# covox.net
KiCad netlist of a schematic drawn in EAGLE
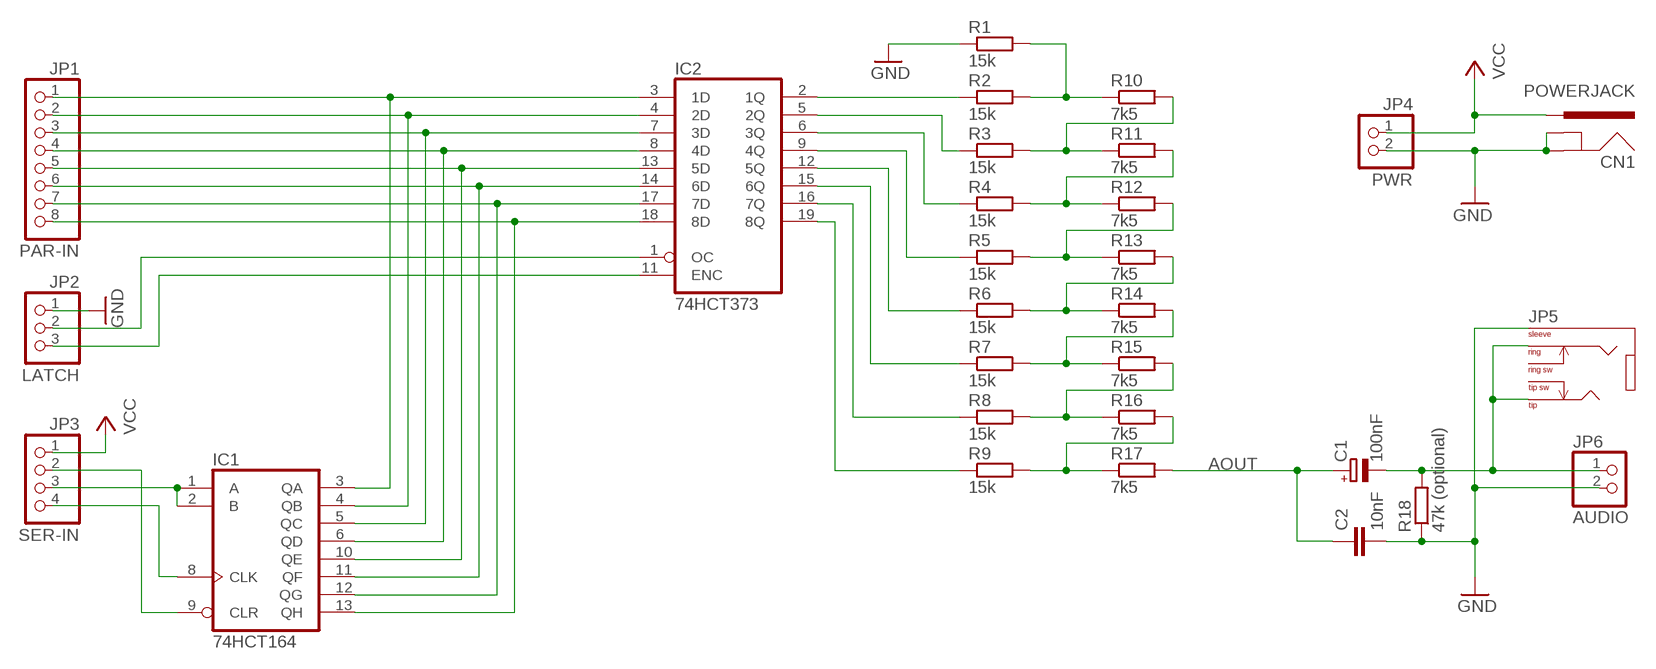
[diagram p0: schematic, sheet 1]

(export (version "E")
  (design (tool "Eeschema 10.0.6"))
  (components
    (comp (ref "C1")
      (value "100nF")
      (footprint "eagle-import:E2-4")
      (libsource (lib "eagle-import") (part "CPOL-EUE2-4"))
    )
    (comp (ref "C2")
      (value "10nF")
      (footprint "eagle-import:C025-025X050")
      (libsource (lib "eagle-import") (part "C-EU025-025X050"))
    )
    (comp (ref "CN1")
      (value "POWERJACK")
      (footprint "eagle-import:POWERJACK_SLOT")
      (libsource (lib "eagle-import") (part "POWERJACK-SLOT"))
    )
    (comp (ref "IC1")
      (value "74HCT164")
      (footprint "eagle-import:DIL14")
      (libsource (lib "eagle-import") (part "74164NHC"))
    )
    (comp (ref "IC2")
      (value "74HCT373")
      (footprint "eagle-import:DIL20")
      (libsource (lib "eagle-import") (part "74373NHCT"))
    )
    (comp (ref "JP1")
      (value "PAR-IN")
      (footprint "eagle-import:1X08")
      (libsource (lib "eagle-import") (part "PINHD-1X8"))
    )
    (comp (ref "JP2")
      (value "LATCH")
      (footprint "eagle-import:1X03")
      (libsource (lib "eagle-import") (part "PINHD-1X3"))
    )
    (comp (ref "JP3")
      (value "SER-IN")
      (footprint "eagle-import:1X04")
      (libsource (lib "eagle-import") (part "PINHD-1X4"))
    )
    (comp (ref "JP4")
      (value "PWR")
      (footprint "eagle-import:1X02")
      (libsource (lib "eagle-import") (part "PINHD-1X2"))
    )
    (comp (ref "JP5")
      (value "AUDIO")
      (footprint "eagle-import:AUDIO-JACK-3.5MM")
      (libsource (lib "eagle-import") (part "AUDIO-JACK-3.5MM"))
    )
    (comp (ref "JP6")
      (value "AUDIO")
      (footprint "eagle-import:1X02")
      (libsource (lib "eagle-import") (part "PINHD-1X2"))
    )
    (comp (ref "R1")
      (value "15k")
      (footprint "eagle-import:0204_7")
      (libsource (lib "eagle-import") (part "R-EU_0204/7"))
    )
    (comp (ref "R2")
      (value "15k")
      (footprint "eagle-import:0204_7")
      (libsource (lib "eagle-import") (part "R-EU_0204/7"))
    )
    (comp (ref "R3")
      (value "15k")
      (footprint "eagle-import:0204_7")
      (libsource (lib "eagle-import") (part "R-EU_0204/7"))
    )
    (comp (ref "R4")
      (value "15k")
      (footprint "eagle-import:0204_7")
      (libsource (lib "eagle-import") (part "R-EU_0204/7"))
    )
    (comp (ref "R5")
      (value "15k")
      (footprint "eagle-import:0204_7")
      (libsource (lib "eagle-import") (part "R-EU_0204/7"))
    )
    (comp (ref "R6")
      (value "15k")
      (footprint "eagle-import:0204_7")
      (libsource (lib "eagle-import") (part "R-EU_0204/7"))
    )
    (comp (ref "R7")
      (value "15k")
      (footprint "eagle-import:0204_7")
      (libsource (lib "eagle-import") (part "R-EU_0204/7"))
    )
    (comp (ref "R8")
      (value "15k")
      (footprint "eagle-import:0204_7")
      (libsource (lib "eagle-import") (part "R-EU_0204/7"))
    )
    (comp (ref "R9")
      (value "15k")
      (footprint "eagle-import:0204_7")
      (libsource (lib "eagle-import") (part "R-EU_0204/7"))
    )
    (comp (ref "R10")
      (value "7k5")
      (footprint "eagle-import:0204_7")
      (libsource (lib "eagle-import") (part "R-EU_0204/7"))
    )
    (comp (ref "R11")
      (value "7k5")
      (footprint "eagle-import:0204_7")
      (libsource (lib "eagle-import") (part "R-EU_0204/7"))
    )
    (comp (ref "R12")
      (value "7k5")
      (footprint "eagle-import:0204_7")
      (libsource (lib "eagle-import") (part "R-EU_0204/7"))
    )
    (comp (ref "R13")
      (value "7k5")
      (footprint "eagle-import:0204_7")
      (libsource (lib "eagle-import") (part "R-EU_0204/7"))
    )
    (comp (ref "R14")
      (value "7k5")
      (footprint "eagle-import:0204_7")
      (libsource (lib "eagle-import") (part "R-EU_0204/7"))
    )
    (comp (ref "R15")
      (value "7k5")
      (footprint "eagle-import:0204_7")
      (libsource (lib "eagle-import") (part "R-EU_0204/7"))
    )
    (comp (ref "R16")
      (value "7k5")
      (footprint "eagle-import:0204_7")
      (libsource (lib "eagle-import") (part "R-EU_0204/7"))
    )
    (comp (ref "R17")
      (value "7k5")
      (footprint "eagle-import:0204_7")
      (libsource (lib "eagle-import") (part "R-EU_0204/7"))
    )
    (comp (ref "R18")
      (value "47k (optional)")
      (footprint "eagle-import:0204_7")
      (libsource (lib "eagle-import") (part "R-EU_0204/7"))
    )
  )
  (nets
    (net (code "1") (name "/AOUT") (class "Default")
      (node (ref "C1") (pin "+") (pinfunction "+_+") (pintype "passive"))
      (node (ref "C2") (pin "1") (pinfunction "1_1") (pintype "passive"))
      (node (ref "R17") (pin "2") (pinfunction "2_2") (pintype "passive"))
    )
    (net (code "2") (name "GND") (class "Default")
      (node (ref "C2") (pin "2") (pinfunction "2_2") (pintype "passive"))
      (node (ref "CN1") (pin "GND@1") (pinfunction "GND_GND@1") (pintype "bidirectional"))
      (node (ref "CN1") (pin "GND@2") (pinfunction "GND_GND@2") (pintype "bidirectional"))
      (node (ref "CN1") (pin "GND@3") (pinfunction "GND_GND@3") (pintype "bidirectional"))
      (node (ref "CN1") (pin "GNDBREAK@1") (pinfunction "GNDBREAK_GNDBREAK@1") (pintype "bidirectional"))
      (node (ref "CN1") (pin "GNDBREAK@2") (pinfunction "GNDBREAK_GNDBREAK@2") (pintype "bidirectional"))
      (node (ref "CN1") (pin "GNDBREAK@3") (pinfunction "GNDBREAK_GNDBREAK@3") (pintype "bidirectional"))
      (node (ref "JP2") (pin "1") (pinfunction "1_1") (pintype "passive"))
      (node (ref "JP4") (pin "2") (pinfunction "2_2") (pintype "passive"))
      (node (ref "JP5") (pin "1") (pinfunction "1_1") (pintype "bidirectional"))
      (node (ref "JP6") (pin "2") (pinfunction "2_2") (pintype "passive"))
      (node (ref "R1") (pin "1") (pinfunction "1_1") (pintype "passive"))
      (node (ref "R18") (pin "1") (pinfunction "1_1") (pintype "passive"))
    )
    (net (code "3") (name "Net-(C1-Pad-)") (class "Default")
      (node (ref "C1") (pin "-") (pinfunction "-_-") (pintype "passive"))
      (node (ref "JP5") (pin "2") (pinfunction "2_2") (pintype "bidirectional"))
      (node (ref "JP5") (pin "3") (pinfunction "3_3") (pintype "bidirectional"))
      (node (ref "JP6") (pin "1") (pinfunction "1_1") (pintype "passive"))
      (node (ref "R18") (pin "2") (pinfunction "2_2") (pintype "passive"))
    )
    (net (code "4") (name "Net-(IC1A-A)") (class "Default")
      (node (ref "IC1") (pin "1") (pinfunction "A_1") (pintype "input"))
      (node (ref "IC1") (pin "2") (pinfunction "B_2") (pintype "input"))
      (node (ref "JP3") (pin "3") (pinfunction "3_3") (pintype "passive"))
    )
    (net (code "5") (name "Net-(IC1A-CLK)") (class "Default")
      (node (ref "IC1") (pin "8") (pinfunction "CLK_8") (pintype "input"))
      (node (ref "JP3") (pin "4") (pinfunction "4_4") (pintype "passive"))
    )
    (net (code "6") (name "Net-(IC1A-CLR)") (class "Default")
      (node (ref "IC1") (pin "9") (pinfunction "CLR_9") (pintype "input"))
      (node (ref "JP3") (pin "2") (pinfunction "2_2") (pintype "passive"))
    )
    (net (code "7") (name "Net-(IC1A-QA)") (class "Default")
      (node (ref "IC1") (pin "3") (pinfunction "QA_3") (pintype "output"))
      (node (ref "IC2") (pin "3") (pinfunction "1D_3") (pintype "input"))
      (node (ref "JP1") (pin "1") (pinfunction "1_1") (pintype "passive"))
    )
    (net (code "8") (name "Net-(IC1A-QB)") (class "Default")
      (node (ref "IC1") (pin "4") (pinfunction "QB_4") (pintype "output"))
      (node (ref "IC2") (pin "4") (pinfunction "2D_4") (pintype "input"))
      (node (ref "JP1") (pin "2") (pinfunction "2_2") (pintype "passive"))
    )
    (net (code "9") (name "Net-(IC1A-QC)") (class "Default")
      (node (ref "IC1") (pin "5") (pinfunction "QC_5") (pintype "output"))
      (node (ref "IC2") (pin "7") (pinfunction "3D_7") (pintype "input"))
      (node (ref "JP1") (pin "3") (pinfunction "3_3") (pintype "passive"))
    )
    (net (code "10") (name "Net-(IC1A-QD)") (class "Default")
      (node (ref "IC1") (pin "6") (pinfunction "QD_6") (pintype "output"))
      (node (ref "IC2") (pin "8") (pinfunction "4D_8") (pintype "input"))
      (node (ref "JP1") (pin "4") (pinfunction "4_4") (pintype "passive"))
    )
    (net (code "11") (name "Net-(IC1A-QE)") (class "Default")
      (node (ref "IC1") (pin "10") (pinfunction "QE_10") (pintype "output"))
      (node (ref "IC2") (pin "13") (pinfunction "5D_13") (pintype "input"))
      (node (ref "JP1") (pin "5") (pinfunction "5_5") (pintype "passive"))
    )
    (net (code "12") (name "Net-(IC1A-QF)") (class "Default")
      (node (ref "IC1") (pin "11") (pinfunction "QF_11") (pintype "output"))
      (node (ref "IC2") (pin "14") (pinfunction "6D_14") (pintype "input"))
      (node (ref "JP1") (pin "6") (pinfunction "6_6") (pintype "passive"))
    )
    (net (code "13") (name "Net-(IC1A-QG)") (class "Default")
      (node (ref "IC1") (pin "12") (pinfunction "QG_12") (pintype "output"))
      (node (ref "IC2") (pin "17") (pinfunction "7D_17") (pintype "input"))
      (node (ref "JP1") (pin "7") (pinfunction "7_7") (pintype "passive"))
    )
    (net (code "14") (name "Net-(IC1A-QH)") (class "Default")
      (node (ref "IC1") (pin "13") (pinfunction "QH_13") (pintype "output"))
      (node (ref "IC2") (pin "18") (pinfunction "8D_18") (pintype "input"))
      (node (ref "JP1") (pin "8") (pinfunction "8_8") (pintype "passive"))
    )
    (net (code "15") (name "Net-(IC2A-1Q)") (class "Default")
      (node (ref "IC2") (pin "2") (pinfunction "1Q_2") (pintype "tri_state"))
      (node (ref "R2") (pin "1") (pinfunction "1_1") (pintype "passive"))
    )
    (net (code "16") (name "Net-(IC2A-2Q)") (class "Default")
      (node (ref "IC2") (pin "5") (pinfunction "2Q_5") (pintype "tri_state"))
      (node (ref "R3") (pin "1") (pinfunction "1_1") (pintype "passive"))
    )
    (net (code "17") (name "Net-(IC2A-3Q)") (class "Default")
      (node (ref "IC2") (pin "6") (pinfunction "3Q_6") (pintype "tri_state"))
      (node (ref "R4") (pin "1") (pinfunction "1_1") (pintype "passive"))
    )
    (net (code "18") (name "Net-(IC2A-4Q)") (class "Default")
      (node (ref "IC2") (pin "9") (pinfunction "4Q_9") (pintype "tri_state"))
      (node (ref "R5") (pin "1") (pinfunction "1_1") (pintype "passive"))
    )
    (net (code "19") (name "Net-(IC2A-5Q)") (class "Default")
      (node (ref "IC2") (pin "12") (pinfunction "5Q_12") (pintype "tri_state"))
      (node (ref "R6") (pin "1") (pinfunction "1_1") (pintype "passive"))
    )
    (net (code "20") (name "Net-(IC2A-6Q)") (class "Default")
      (node (ref "IC2") (pin "15") (pinfunction "6Q_15") (pintype "tri_state"))
      (node (ref "R7") (pin "1") (pinfunction "1_1") (pintype "passive"))
    )
    (net (code "21") (name "Net-(IC2A-7Q)") (class "Default")
      (node (ref "IC2") (pin "16") (pinfunction "7Q_16") (pintype "tri_state"))
      (node (ref "R8") (pin "1") (pinfunction "1_1") (pintype "passive"))
    )
    (net (code "22") (name "Net-(IC2A-8Q)") (class "Default")
      (node (ref "IC2") (pin "19") (pinfunction "8Q_19") (pintype "tri_state"))
      (node (ref "R9") (pin "1") (pinfunction "1_1") (pintype "passive"))
    )
    (net (code "23") (name "Net-(IC2A-ENC)") (class "Default")
      (node (ref "IC2") (pin "11") (pinfunction "ENC_11") (pintype "input"))
      (node (ref "JP2") (pin "3") (pinfunction "3_3") (pintype "passive"))
    )
    (net (code "24") (name "Net-(IC2A-OC)") (class "Default")
      (node (ref "IC2") (pin "1") (pinfunction "OC_1") (pintype "input"))
      (node (ref "JP2") (pin "2") (pinfunction "2_2") (pintype "passive"))
    )
    (net (code "25") (name "Net-(R1-Pad2)") (class "Default")
      (node (ref "R1") (pin "2") (pinfunction "2_2") (pintype "passive"))
      (node (ref "R10") (pin "1") (pinfunction "1_1") (pintype "passive"))
      (node (ref "R2") (pin "2") (pinfunction "2_2") (pintype "passive"))
    )
    (net (code "26") (name "Net-(R10-Pad2)") (class "Default")
      (node (ref "R10") (pin "2") (pinfunction "2_2") (pintype "passive"))
      (node (ref "R11") (pin "1") (pinfunction "1_1") (pintype "passive"))
      (node (ref "R3") (pin "2") (pinfunction "2_2") (pintype "passive"))
    )
    (net (code "27") (name "Net-(R11-Pad2)") (class "Default")
      (node (ref "R11") (pin "2") (pinfunction "2_2") (pintype "passive"))
      (node (ref "R12") (pin "1") (pinfunction "1_1") (pintype "passive"))
      (node (ref "R4") (pin "2") (pinfunction "2_2") (pintype "passive"))
    )
    (net (code "28") (name "Net-(R12-Pad2)") (class "Default")
      (node (ref "R12") (pin "2") (pinfunction "2_2") (pintype "passive"))
      (node (ref "R13") (pin "1") (pinfunction "1_1") (pintype "passive"))
      (node (ref "R5") (pin "2") (pinfunction "2_2") (pintype "passive"))
    )
    (net (code "29") (name "Net-(R13-Pad2)") (class "Default")
      (node (ref "R13") (pin "2") (pinfunction "2_2") (pintype "passive"))
      (node (ref "R14") (pin "1") (pinfunction "1_1") (pintype "passive"))
      (node (ref "R6") (pin "2") (pinfunction "2_2") (pintype "passive"))
    )
    (net (code "30") (name "Net-(R14-Pad2)") (class "Default")
      (node (ref "R14") (pin "2") (pinfunction "2_2") (pintype "passive"))
      (node (ref "R15") (pin "1") (pinfunction "1_1") (pintype "passive"))
      (node (ref "R7") (pin "2") (pinfunction "2_2") (pintype "passive"))
    )
    (net (code "31") (name "Net-(R15-Pad2)") (class "Default")
      (node (ref "R15") (pin "2") (pinfunction "2_2") (pintype "passive"))
      (node (ref "R16") (pin "1") (pinfunction "1_1") (pintype "passive"))
      (node (ref "R8") (pin "2") (pinfunction "2_2") (pintype "passive"))
    )
    (net (code "32") (name "Net-(R16-Pad2)") (class "Default")
      (node (ref "R16") (pin "2") (pinfunction "2_2") (pintype "passive"))
      (node (ref "R17") (pin "1") (pinfunction "1_1") (pintype "passive"))
      (node (ref "R9") (pin "2") (pinfunction "2_2") (pintype "passive"))
    )
    (net (code "33") (name "VCC") (class "Default")
      (node (ref "CN1") (pin "PWR@1") (pinfunction "PWR_PWR@1") (pintype "bidirectional"))
      (node (ref "CN1") (pin "PWR@2") (pinfunction "PWR_PWR@2") (pintype "bidirectional"))
      (node (ref "CN1") (pin "PWR@3") (pinfunction "PWR_PWR@3") (pintype "bidirectional"))
      (node (ref "JP3") (pin "1") (pinfunction "1_1") (pintype "passive"))
      (node (ref "JP4") (pin "1") (pinfunction "1_1") (pintype "passive"))
    )
    (net (code "34") (name "unconnected-(JP5-Pad4)") (class "Default")
      (node (ref "JP5") (pin "4") (pinfunction "4_4") (pintype "bidirectional"))
    )
    (net (code "35") (name "unconnected-(JP5-Pad5)") (class "Default")
      (node (ref "JP5") (pin "5") (pinfunction "5_5") (pintype "bidirectional"))
    )
  )
)
